# versi_satu.net
KiCad netlist of a schematic drawn in EAGLE
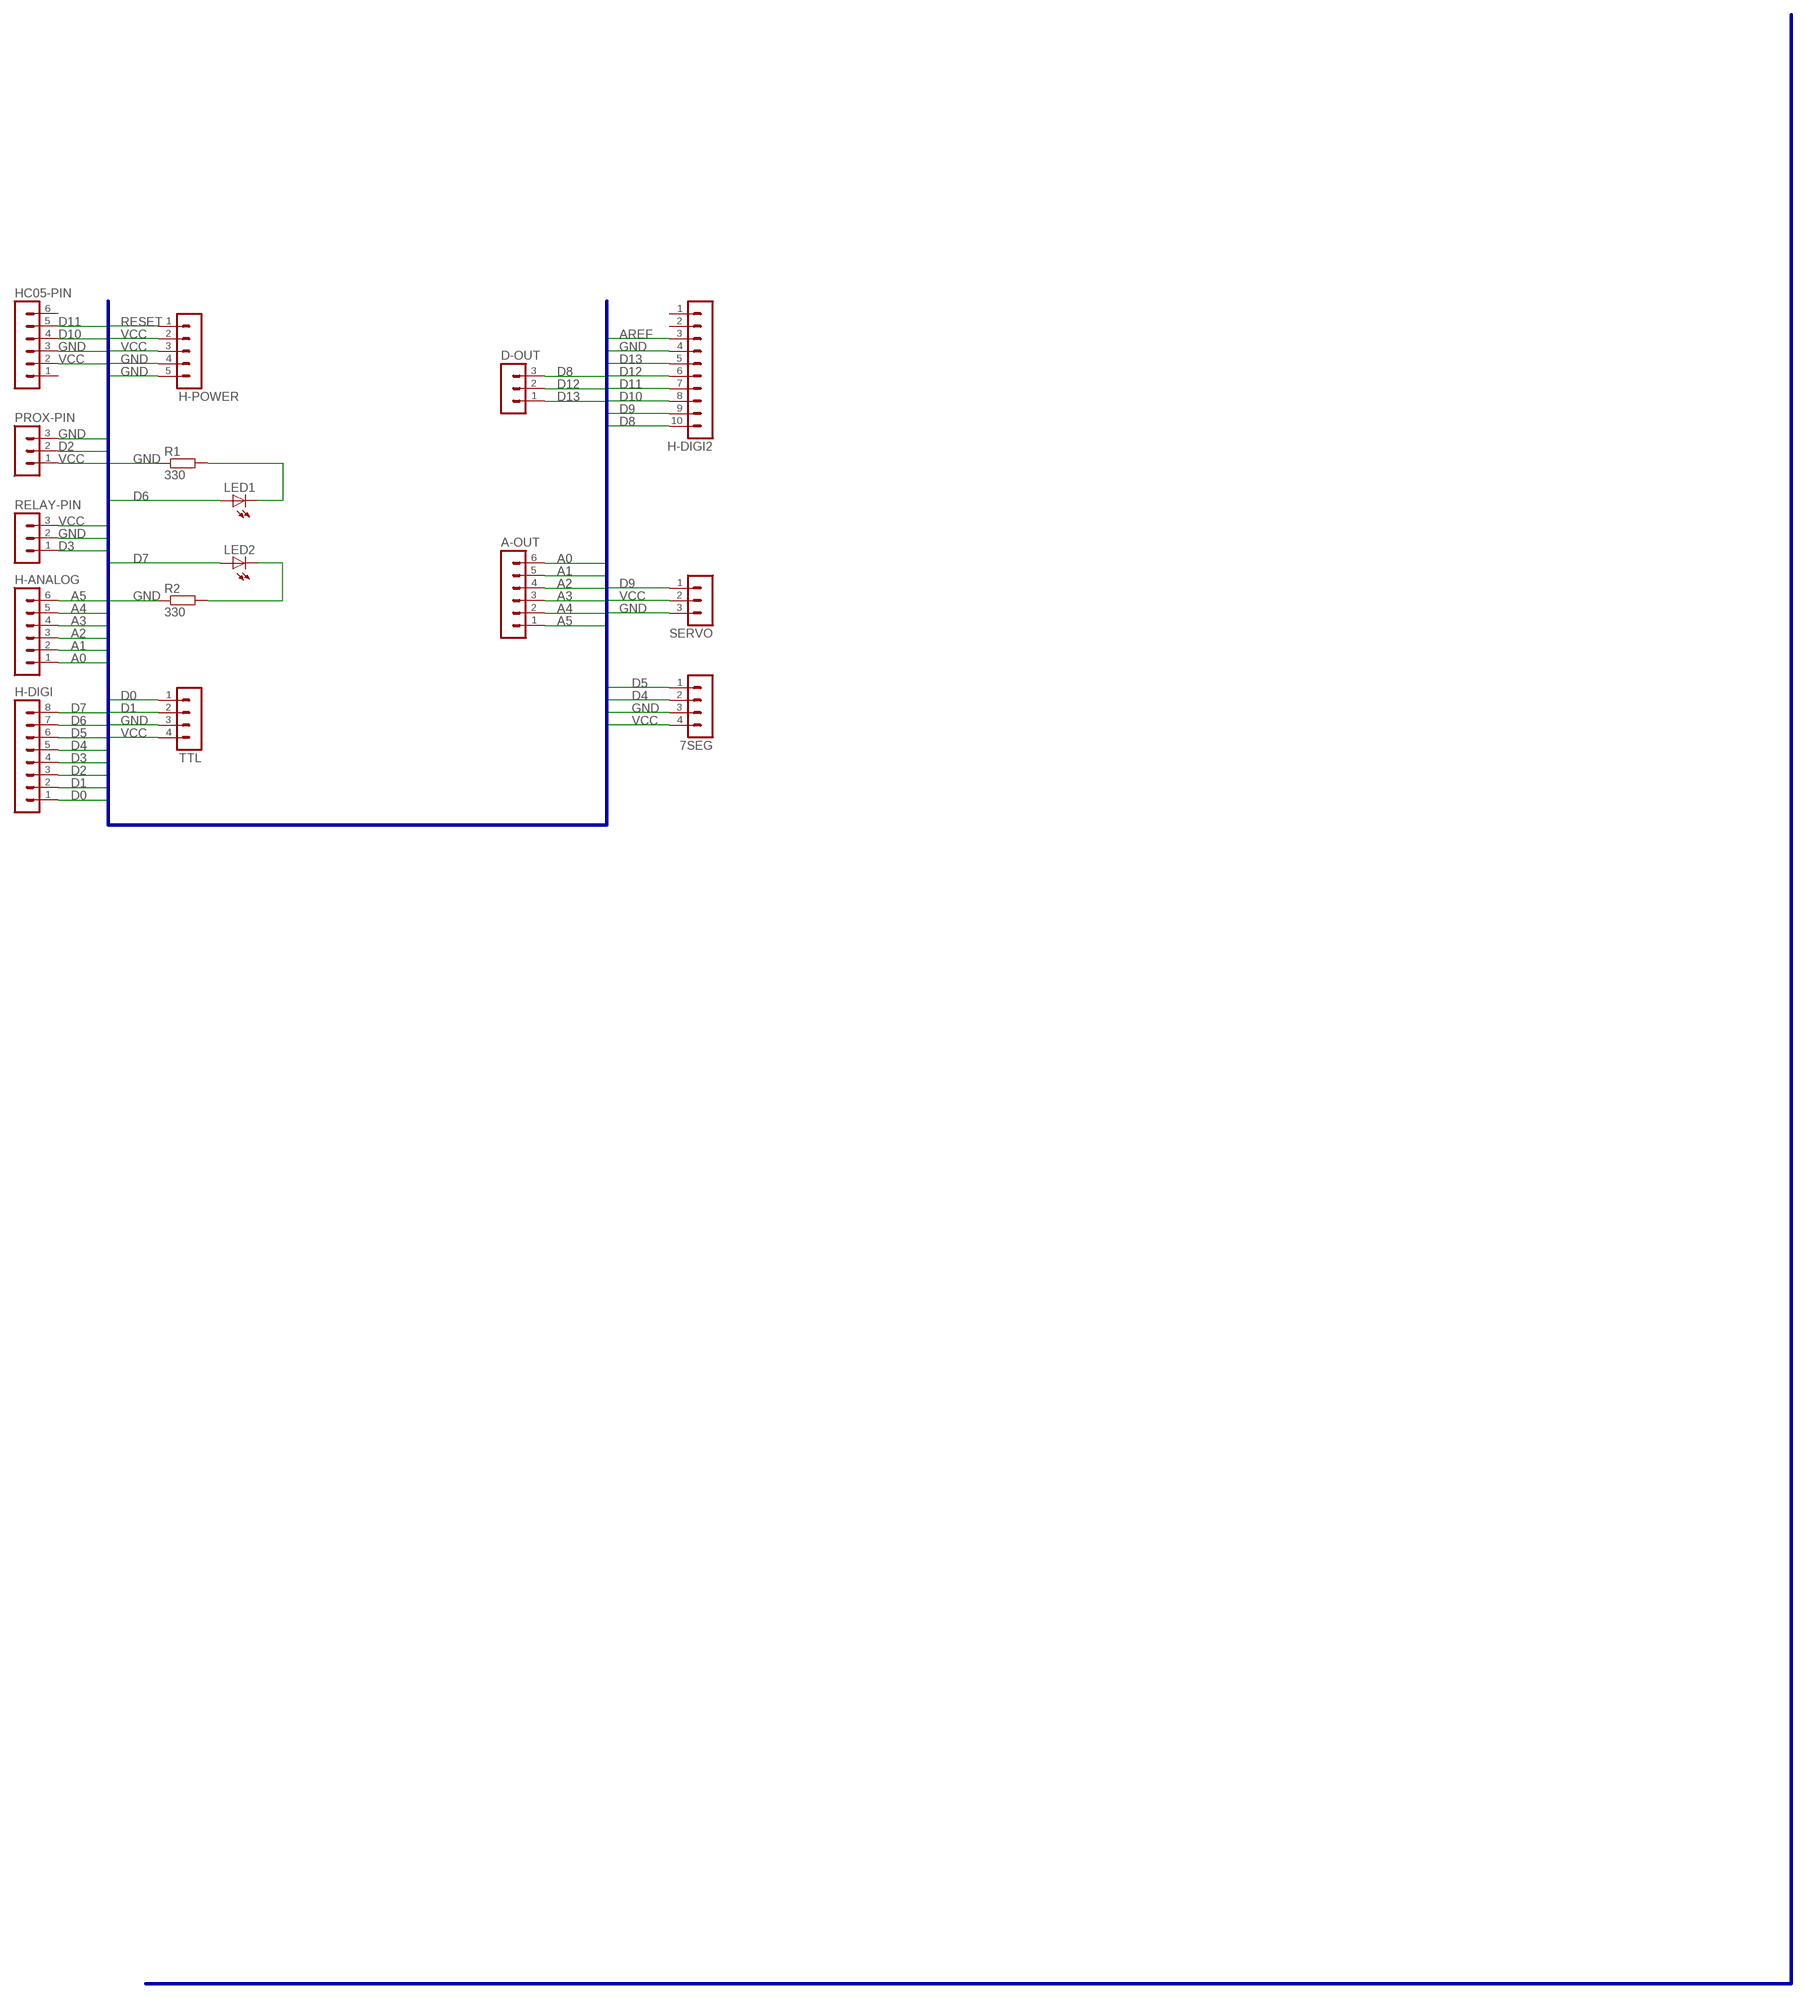
[diagram p0: schematic, sheet 1]

(export (version "E")
  (design (tool "Eeschema 10.0.6"))
  (components
    (comp (ref "7SEG")
      (value "MA04-1")
      (footprint "eagle-import:MA04-1")
      (libsource (lib "eagle-import") (part "MA04-1"))
    )
    (comp (ref "A-OUT")
      (value "MA06-1")
      (footprint "eagle-import:MA06-1")
      (libsource (lib "eagle-import") (part "MA06-1"))
    )
    (comp (ref "D-OUT")
      (value "MA03-1")
      (footprint "eagle-import:MA03-1")
      (libsource (lib "eagle-import") (part "MA03-1"))
    )
    (comp (ref "H-ANALOG")
      (value "MA06-1")
      (footprint "eagle-import:MA06-1")
      (libsource (lib "eagle-import") (part "MA06-1"))
    )
    (comp (ref "H-DIGI")
      (value "MA08-1")
      (footprint "eagle-import:MA08-1")
      (libsource (lib "eagle-import") (part "MA08-1"))
    )
    (comp (ref "H-DIGI2")
      (value "MA10-1")
      (footprint "eagle-import:MA10-1")
      (libsource (lib "eagle-import") (part "MA10-1"))
    )
    (comp (ref "H-POWER")
      (value "MA05-1")
      (footprint "eagle-import:MA05-1")
      (libsource (lib "eagle-import") (part "MA05-1"))
    )
    (comp (ref "HC05-PIN")
      (value "MA06-1")
      (footprint "eagle-import:MA06-1")
      (libsource (lib "eagle-import") (part "MA06-1"))
    )
    (comp (ref "LED1")
      (value "LED5MM")
      (footprint "eagle-import:LED5MM")
      (libsource (lib "eagle-import") (part "LED5MM"))
    )
    (comp (ref "LED2")
      (value "LED5MM")
      (footprint "eagle-import:LED5MM")
      (libsource (lib "eagle-import") (part "LED5MM"))
    )
    (comp (ref "PROX-PIN")
      (value "MA03-1")
      (footprint "eagle-import:MA03-1")
      (libsource (lib "eagle-import") (part "MA03-1"))
    )
    (comp (ref "R1")
      (value "330")
      (footprint "eagle-import:0207_10")
      (libsource (lib "eagle-import") (part "R-EU_0207/10"))
    )
    (comp (ref "R2")
      (value "330")
      (footprint "eagle-import:0207_10")
      (libsource (lib "eagle-import") (part "R-EU_0207/10"))
    )
    (comp (ref "RELAY-PIN")
      (value "MA03-1")
      (footprint "eagle-import:MA03-1")
      (libsource (lib "eagle-import") (part "MA03-1"))
    )
    (comp (ref "SERVO")
      (value "MA03-1")
      (footprint "eagle-import:MA03-1")
      (libsource (lib "eagle-import") (part "MA03-1"))
    )
    (comp (ref "TTL")
      (value "MA04-1")
      (footprint "eagle-import:MA04-1")
      (libsource (lib "eagle-import") (part "MA04-1"))
    )
  )
  (nets
    (net (code "5") (name "/A0") (class "Default")
      (node (ref "A-OUT") (pin "6") (pinfunction "6_6") (pintype "passive"))
      (node (ref "H-ANALOG") (pin "1") (pinfunction "1_1") (pintype "passive"))
    )
    (net (code "6") (name "/A1") (class "Default")
      (node (ref "A-OUT") (pin "5") (pinfunction "5_5") (pintype "passive"))
      (node (ref "H-ANALOG") (pin "2") (pinfunction "2_2") (pintype "passive"))
    )
    (net (code "7") (name "/A2") (class "Default")
      (node (ref "A-OUT") (pin "4") (pinfunction "4_4") (pintype "passive"))
      (node (ref "H-ANALOG") (pin "3") (pinfunction "3_3") (pintype "passive"))
    )
    (net (code "8") (name "/A3") (class "Default")
      (node (ref "A-OUT") (pin "3") (pinfunction "3_3") (pintype "passive"))
      (node (ref "H-ANALOG") (pin "4") (pinfunction "4_4") (pintype "passive"))
    )
    (net (code "9") (name "/A4") (class "Default")
      (node (ref "A-OUT") (pin "2") (pinfunction "2_2") (pintype "passive"))
      (node (ref "H-ANALOG") (pin "5") (pinfunction "5_5") (pintype "passive"))
    )
    (net (code "10") (name "/A5") (class "Default")
      (node (ref "A-OUT") (pin "1") (pinfunction "1_1") (pintype "passive"))
      (node (ref "H-ANALOG") (pin "6") (pinfunction "6_6") (pintype "passive"))
    )
    (net (code "11") (name "/AREF") (class "Default")
      (node (ref "H-DIGI2") (pin "3") (pinfunction "3_3") (pintype "passive"))
    )
    (net (code "12") (name "/D0") (class "Default")
      (node (ref "H-DIGI") (pin "1") (pinfunction "1_1") (pintype "passive"))
      (node (ref "TTL") (pin "1") (pinfunction "1_1") (pintype "passive"))
    )
    (net (code "13") (name "/D1") (class "Default")
      (node (ref "H-DIGI") (pin "2") (pinfunction "2_2") (pintype "passive"))
      (node (ref "TTL") (pin "2") (pinfunction "2_2") (pintype "passive"))
    )
    (net (code "14") (name "/D2") (class "Default")
      (node (ref "H-DIGI") (pin "3") (pinfunction "3_3") (pintype "passive"))
      (node (ref "PROX-PIN") (pin "2") (pinfunction "2_2") (pintype "passive"))
    )
    (net (code "15") (name "/D3") (class "Default")
      (node (ref "H-DIGI") (pin "4") (pinfunction "4_4") (pintype "passive"))
      (node (ref "RELAY-PIN") (pin "1") (pinfunction "1_1") (pintype "passive"))
    )
    (net (code "16") (name "/D4") (class "Default")
      (node (ref "7SEG") (pin "2") (pinfunction "2_2") (pintype "passive"))
      (node (ref "H-DIGI") (pin "5") (pinfunction "5_5") (pintype "passive"))
    )
    (net (code "17") (name "/D5") (class "Default")
      (node (ref "7SEG") (pin "1") (pinfunction "1_1") (pintype "passive"))
      (node (ref "H-DIGI") (pin "6") (pinfunction "6_6") (pintype "passive"))
    )
    (net (code "18") (name "/D6") (class "Default")
      (node (ref "H-DIGI") (pin "7") (pinfunction "7_7") (pintype "passive"))
      (node (ref "LED1") (pin "A") (pinfunction "A_A") (pintype "passive"))
    )
    (net (code "19") (name "/D7") (class "Default")
      (node (ref "H-DIGI") (pin "8") (pinfunction "8_8") (pintype "passive"))
      (node (ref "LED2") (pin "A") (pinfunction "A_A") (pintype "passive"))
    )
    (net (code "20") (name "/D8") (class "Default")
      (node (ref "D-OUT") (pin "3") (pinfunction "3_3") (pintype "passive"))
      (node (ref "H-DIGI2") (pin "10") (pinfunction "10_10") (pintype "passive"))
    )
    (net (code "21") (name "/D9") (class "Default")
      (node (ref "H-DIGI2") (pin "9") (pinfunction "9_9") (pintype "passive"))
      (node (ref "SERVO") (pin "1") (pinfunction "1_1") (pintype "passive"))
    )
    (net (code "22") (name "/D10") (class "Default")
      (node (ref "H-DIGI2") (pin "8") (pinfunction "8_8") (pintype "passive"))
      (node (ref "HC05-PIN") (pin "4") (pinfunction "4_4") (pintype "passive"))
    )
    (net (code "23") (name "/D11") (class "Default")
      (node (ref "H-DIGI2") (pin "7") (pinfunction "7_7") (pintype "passive"))
      (node (ref "HC05-PIN") (pin "5") (pinfunction "5_5") (pintype "passive"))
    )
    (net (code "24") (name "/D12") (class "Default")
      (node (ref "D-OUT") (pin "2") (pinfunction "2_2") (pintype "passive"))
      (node (ref "H-DIGI2") (pin "6") (pinfunction "6_6") (pintype "passive"))
    )
    (net (code "25") (name "/D13") (class "Default")
      (node (ref "D-OUT") (pin "1") (pinfunction "1_1") (pintype "passive"))
      (node (ref "H-DIGI2") (pin "5") (pinfunction "5_5") (pintype "passive"))
    )
    (net (code "26") (name "/GND") (class "Default")
      (node (ref "7SEG") (pin "3") (pinfunction "3_3") (pintype "passive"))
      (node (ref "H-DIGI2") (pin "4") (pinfunction "4_4") (pintype "passive"))
      (node (ref "H-POWER") (pin "4") (pinfunction "4_4") (pintype "passive"))
      (node (ref "H-POWER") (pin "5") (pinfunction "5_5") (pintype "passive"))
      (node (ref "HC05-PIN") (pin "3") (pinfunction "3_3") (pintype "passive"))
      (node (ref "PROX-PIN") (pin "3") (pinfunction "3_3") (pintype "passive"))
      (node (ref "R1") (pin "1") (pinfunction "1_1") (pintype "passive"))
      (node (ref "R2") (pin "1") (pinfunction "1_1") (pintype "passive"))
      (node (ref "RELAY-PIN") (pin "2") (pinfunction "2_2") (pintype "passive"))
      (node (ref "SERVO") (pin "3") (pinfunction "3_3") (pintype "passive"))
      (node (ref "TTL") (pin "3") (pinfunction "3_3") (pintype "passive"))
    )
    (net (code "27") (name "/RESET") (class "Default")
      (node (ref "H-POWER") (pin "1") (pinfunction "1_1") (pintype "passive"))
    )
    (net (code "28") (name "/VCC") (class "Default")
      (node (ref "7SEG") (pin "4") (pinfunction "4_4") (pintype "passive"))
      (node (ref "H-POWER") (pin "2") (pinfunction "2_2") (pintype "passive"))
      (node (ref "H-POWER") (pin "3") (pinfunction "3_3") (pintype "passive"))
      (node (ref "HC05-PIN") (pin "2") (pinfunction "2_2") (pintype "passive"))
      (node (ref "PROX-PIN") (pin "1") (pinfunction "1_1") (pintype "passive"))
      (node (ref "RELAY-PIN") (pin "3") (pinfunction "3_3") (pintype "passive"))
      (node (ref "SERVO") (pin "2") (pinfunction "2_2") (pintype "passive"))
      (node (ref "TTL") (pin "4") (pinfunction "4_4") (pintype "passive"))
    )
    (net (code "30") (name "Net-(LED1-C)") (class "Default")
      (node (ref "LED1") (pin "K") (pinfunction "C_K") (pintype "passive"))
      (node (ref "R1") (pin "2") (pinfunction "2_2") (pintype "passive"))
    )
    (net (code "31") (name "Net-(LED2-C)") (class "Default")
      (node (ref "LED2") (pin "K") (pinfunction "C_K") (pintype "passive"))
      (node (ref "R2") (pin "2") (pinfunction "2_2") (pintype "passive"))
    )
    (net (code "32") (name "unconnected-(H-DIGI2-Pad1)") (class "Default")
      (node (ref "H-DIGI2") (pin "1") (pinfunction "1_1") (pintype "passive"))
    )
    (net (code "33") (name "unconnected-(H-DIGI2-Pad2)") (class "Default")
      (node (ref "H-DIGI2") (pin "2") (pinfunction "2_2") (pintype "passive"))
    )
    (net (code "34") (name "unconnected-(HC05-PIN-Pad1)") (class "Default")
      (node (ref "HC05-PIN") (pin "1") (pinfunction "1_1") (pintype "passive"))
    )
    (net (code "35") (name "unconnected-(HC05-PIN-Pad6)") (class "Default")
      (node (ref "HC05-PIN") (pin "6") (pinfunction "6_6") (pintype "passive"))
    )
  )
)
